# V-00321-01.net
KiCad netlist of a schematic drawn in EAGLE
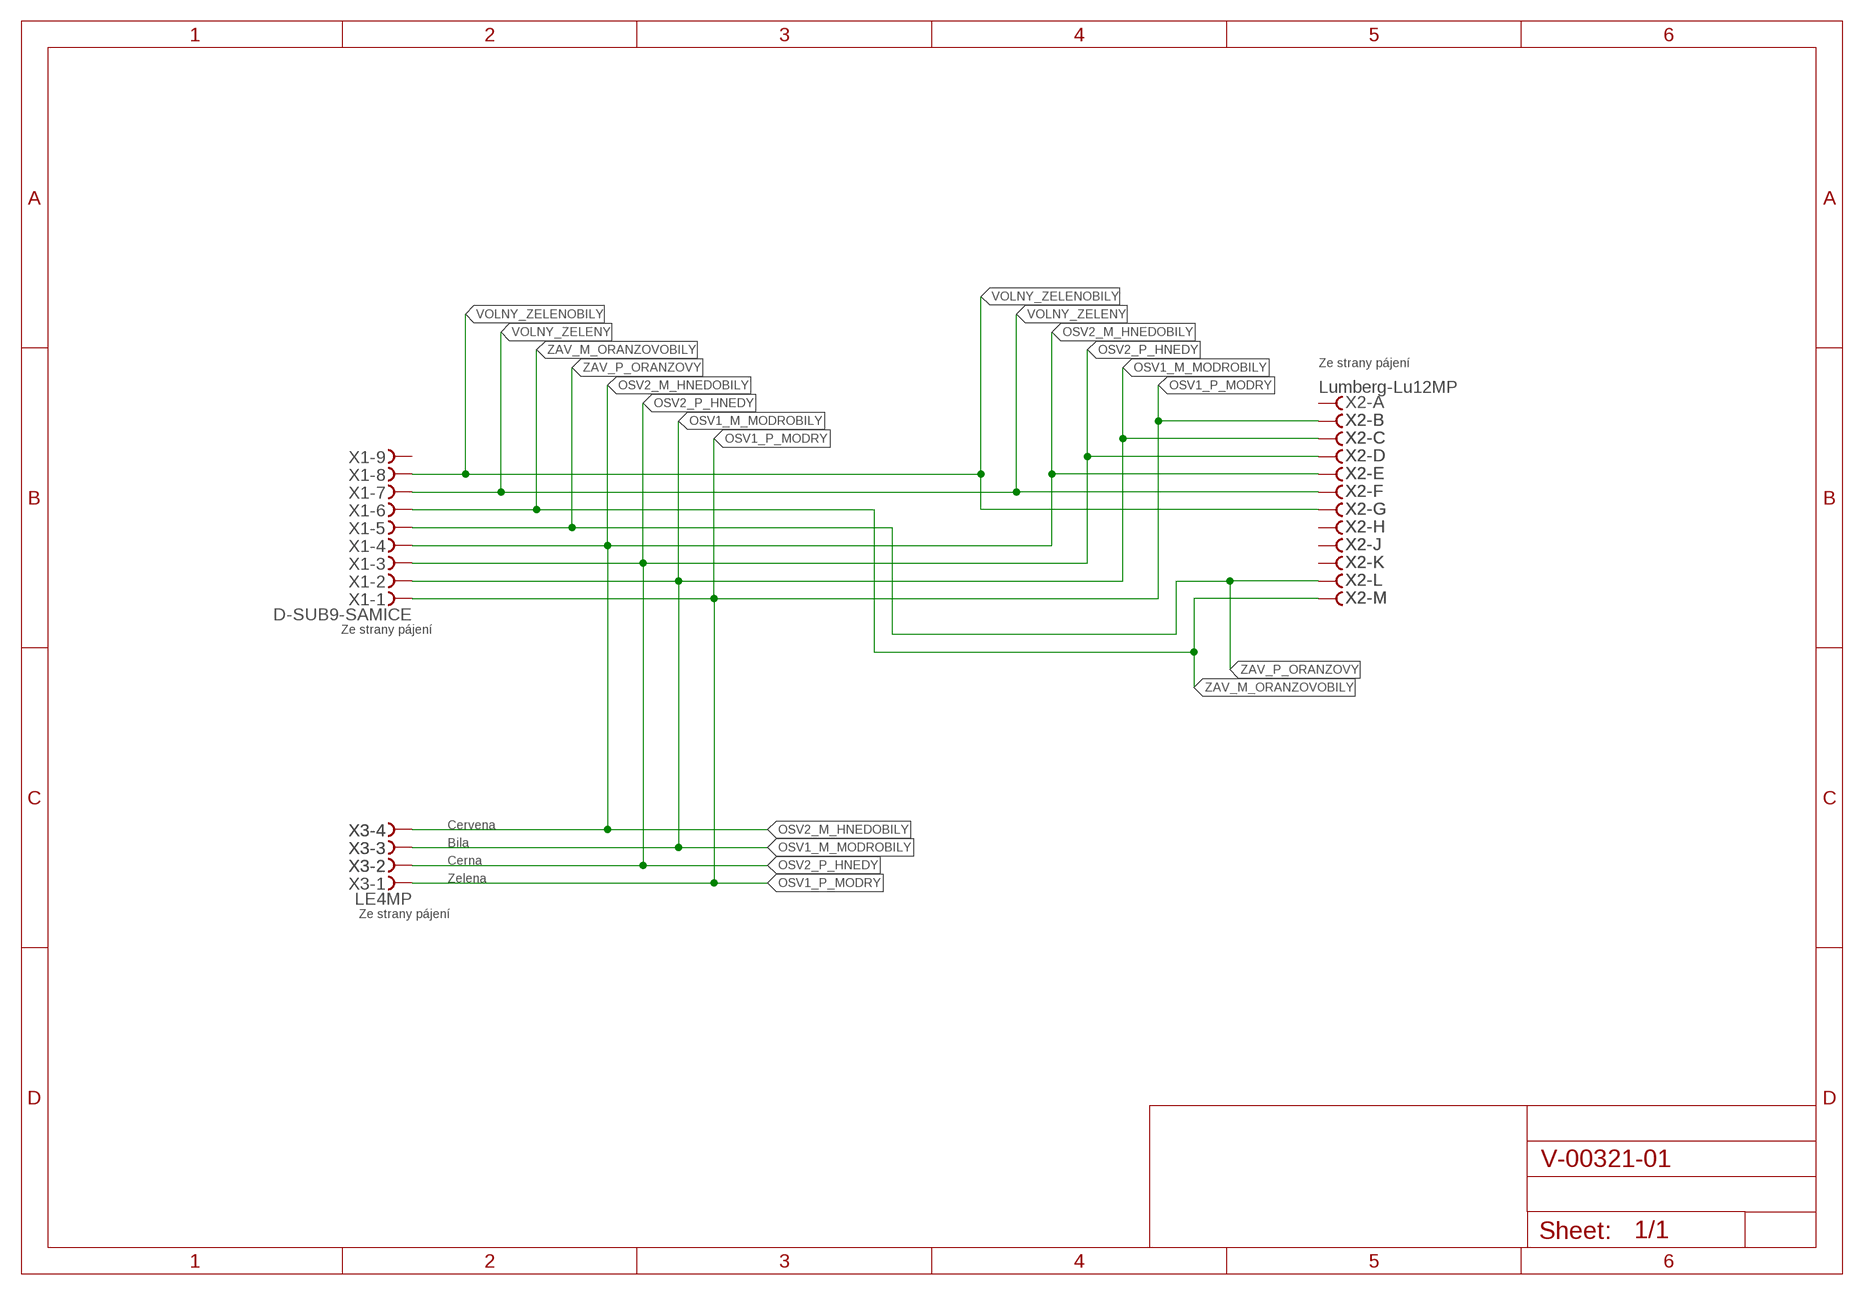
[diagram p0: schematic, sheet 1]

(export (version "E")
  (design (tool "Eeschema 10.0.6"))
  (components
    (comp (ref "X1")
      (value "D-SUB9-SAMICE")
      (footprint "eagle-import:H2M09ST")
      (libsource (lib "eagle-import") (part "D-SUB9-H2M09ST"))
    )
    (comp (ref "X2")
      (value "Lumberg-Lu12MP")
      (footprint "eagle-import:LU12MP")
      (libsource (lib "eagle-import") (part "LU12MP"))
    )
    (comp (ref "X3")
      (value "LE4MP")
      (footprint "eagle-import:LE4MP")
      (libsource (lib "eagle-import") (part "LE4MP"))
    )
  )
  (nets
    (net (code "1") (name "OSV1_M_MODROBILY") (class "Default")
      (node (ref "X1") (pin "2") (pinfunction "F_2") (pintype "passive"))
      (node (ref "X2") (pin "C") (pinfunction "F_C") (pintype "passive"))
      (node (ref "X3") (pin "3") (pinfunction "F_3") (pintype "passive"))
    )
    (net (code "2") (name "OSV1_P_MODRY") (class "Default")
      (node (ref "X1") (pin "1") (pinfunction "F_1") (pintype "passive"))
      (node (ref "X2") (pin "B") (pinfunction "F_B") (pintype "passive"))
      (node (ref "X3") (pin "1") (pinfunction "F_1") (pintype "passive"))
    )
    (net (code "3") (name "OSV2_M_HNEDOBILY") (class "Default")
      (node (ref "X1") (pin "4") (pinfunction "F_4") (pintype "passive"))
      (node (ref "X2") (pin "E") (pinfunction "F_E") (pintype "passive"))
      (node (ref "X3") (pin "4") (pinfunction "F_4") (pintype "passive"))
    )
    (net (code "4") (name "OSV2_P_HNEDY") (class "Default")
      (node (ref "X1") (pin "3") (pinfunction "F_3") (pintype "passive"))
      (node (ref "X2") (pin "D") (pinfunction "F_D") (pintype "passive"))
      (node (ref "X3") (pin "2") (pinfunction "F_2") (pintype "passive"))
    )
    (net (code "5") (name "VOLNY_ZELENOBILY") (class "Default")
      (node (ref "X1") (pin "8") (pinfunction "F_8") (pintype "passive"))
      (node (ref "X2") (pin "G") (pinfunction "F_G") (pintype "passive"))
    )
    (net (code "6") (name "VOLNY_ZELENY") (class "Default")
      (node (ref "X1") (pin "7") (pinfunction "F_7") (pintype "passive"))
      (node (ref "X2") (pin "F") (pinfunction "F_F") (pintype "passive"))
    )
    (net (code "7") (name "ZAV_M_ORANZOVOBILY") (class "Default")
      (node (ref "X1") (pin "6") (pinfunction "F_6") (pintype "passive"))
      (node (ref "X2") (pin "M") (pinfunction "F_M") (pintype "passive"))
    )
    (net (code "8") (name "ZAV_P_ORANZOVY") (class "Default")
      (node (ref "X1") (pin "5") (pinfunction "F_5") (pintype "passive"))
      (node (ref "X2") (pin "L") (pinfunction "F_L") (pintype "passive"))
    )
    (net (code "9") (name "unconnected-(X1I-F-Pad9)") (class "Default")
      (node (ref "X1") (pin "9") (pinfunction "F_9") (pintype "passive"))
    )
    (net (code "10") (name "unconnected-(X2A-F-PadA)") (class "Default")
      (node (ref "X2") (pin "A") (pinfunction "F_A") (pintype "passive"))
    )
    (net (code "11") (name "unconnected-(X2H-F-PadH)") (class "Default")
      (node (ref "X2") (pin "H") (pinfunction "F_H") (pintype "passive"))
    )
    (net (code "12") (name "unconnected-(X2I-F-PadJ)") (class "Default")
      (node (ref "X2") (pin "J") (pinfunction "F_J") (pintype "passive"))
    )
    (net (code "13") (name "unconnected-(X2J-F-PadK)") (class "Default")
      (node (ref "X2") (pin "K") (pinfunction "F_K") (pintype "passive"))
    )
  )
)
